# US_SB_Meteo.net
KiCad netlist of a schematic drawn in Altium Designer
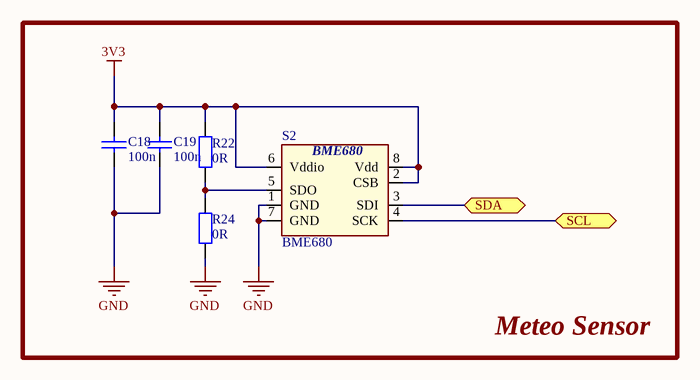
[diagram p0: US_SB_Meteo.SchDoc]

(export (version "E")
  (design (tool "Eeschema 10.0.6"))
  (components
    (comp (ref "C18")
      (value "100n")
      (footprint "C0603_IPC_HD")
      (description "CAP CER 0.1UF 16V X7R 0603")
      (fields
        (field (name "MANUFACTURER") "Samsung Electro-Mechanics")
        (field (name "MANUFACTURER PART NUMBER") "CL10B104KO8NNNC")
      )
      (libsource (lib "alfasat_parts_lib") (part "CL10B104KO8NNNC"))
    )
    (comp (ref "C19")
      (value "100n")
      (footprint "C0603_IPC_HD")
      (description "CAP CER 0.1UF 16V X7R 0603")
      (fields
        (field (name "MANUFACTURER") "Samsung Electro-Mechanics")
        (field (name "MANUFACTURER PART NUMBER") "CL10B104KO8NNNC")
      )
      (libsource (lib "alfasat_parts_lib") (part "CL10B104KO8NNNC"))
    )
    (comp (ref "R22")
      (value "0R")
      (footprint "R0603_IPC_MD")
      (description "RES SMD 0 OHM JUMPER 1/10W 0603")
      (fields
        (field (name "MANUFACTURER") "Bourns Inc.")
        (field (name "MANUFACTURER PART NUMBER") "CR0603-J/-000ELF")
      )
      (libsource (lib "alfasat_lib") (part "CR0603-J/-000ELF"))
    )
    (comp (ref "R24")
      (value "0R")
      (footprint "R0603_IPC_MD")
      (description "RES SMD 0 OHM JUMPER 1/10W 0603")
      (fields
        (field (name "MANUFACTURER") "Bourns Inc.")
        (field (name "MANUFACTURER PART NUMBER") "CR0603-J/-000ELF")
      )
      (libsource (lib "alfasat_lib") (part "CR0603-J/-000ELF"))
    )
    (comp (ref "S2")
      (value "BME680")
      (footprint "BME680")
      (description "Gas, Humidity, Pressure, Temperature Sensor I²C, SPI Output")
      (fields (field (name "MANUFACTURER") "Bosch Sensortec"))
      (libsource (lib "alfasat_lib_eps") (part "BME680"))
    )
  )
  (nets
    (net (code "1") (name "/SCL") (class "Default")
      (node (ref "S2") (pin "4") (pinfunction "SCK_4") (pintype "passive"))
    )
    (net (code "2") (name "/SDA") (class "Default")
      (node (ref "S2") (pin "3") (pinfunction "SDI_3") (pintype "passive"))
    )
    (net (code "3") (name "3V3") (class "Default")
      (node (ref "C18") (pin "2") (pinfunction "2_2") (pintype "passive"))
      (node (ref "C19") (pin "2") (pinfunction "2_2") (pintype "passive"))
      (node (ref "R22") (pin "2") (pinfunction "2_2") (pintype "passive"))
      (node (ref "S2") (pin "2") (pinfunction "CSB_2") (pintype "passive"))
      (node (ref "S2") (pin "6") (pinfunction "Vddio_6") (pintype "passive"))
      (node (ref "S2") (pin "8") (pinfunction "Vdd_8") (pintype "passive"))
    )
    (net (code "4") (name "GND") (class "Default")
      (node (ref "C18") (pin "1") (pinfunction "1_1") (pintype "passive"))
      (node (ref "C19") (pin "1") (pinfunction "1_1") (pintype "passive"))
      (node (ref "R24") (pin "1") (pinfunction "1_1") (pintype "passive"))
      (node (ref "S2") (pin "1") (pinfunction "GND_1") (pintype "passive"))
      (node (ref "S2") (pin "7") (pinfunction "GND_7") (pintype "passive"))
    )
    (net (code "5") (name "Net-(S2-SDO)") (class "Default")
      (node (ref "R22") (pin "1") (pinfunction "1_1") (pintype "passive"))
      (node (ref "R24") (pin "2") (pinfunction "2_2") (pintype "passive"))
      (node (ref "S2") (pin "5") (pinfunction "SDO_5") (pintype "passive"))
    )
  )
)
